# M360.net
KiCad netlist of a schematic drawn in EAGLE
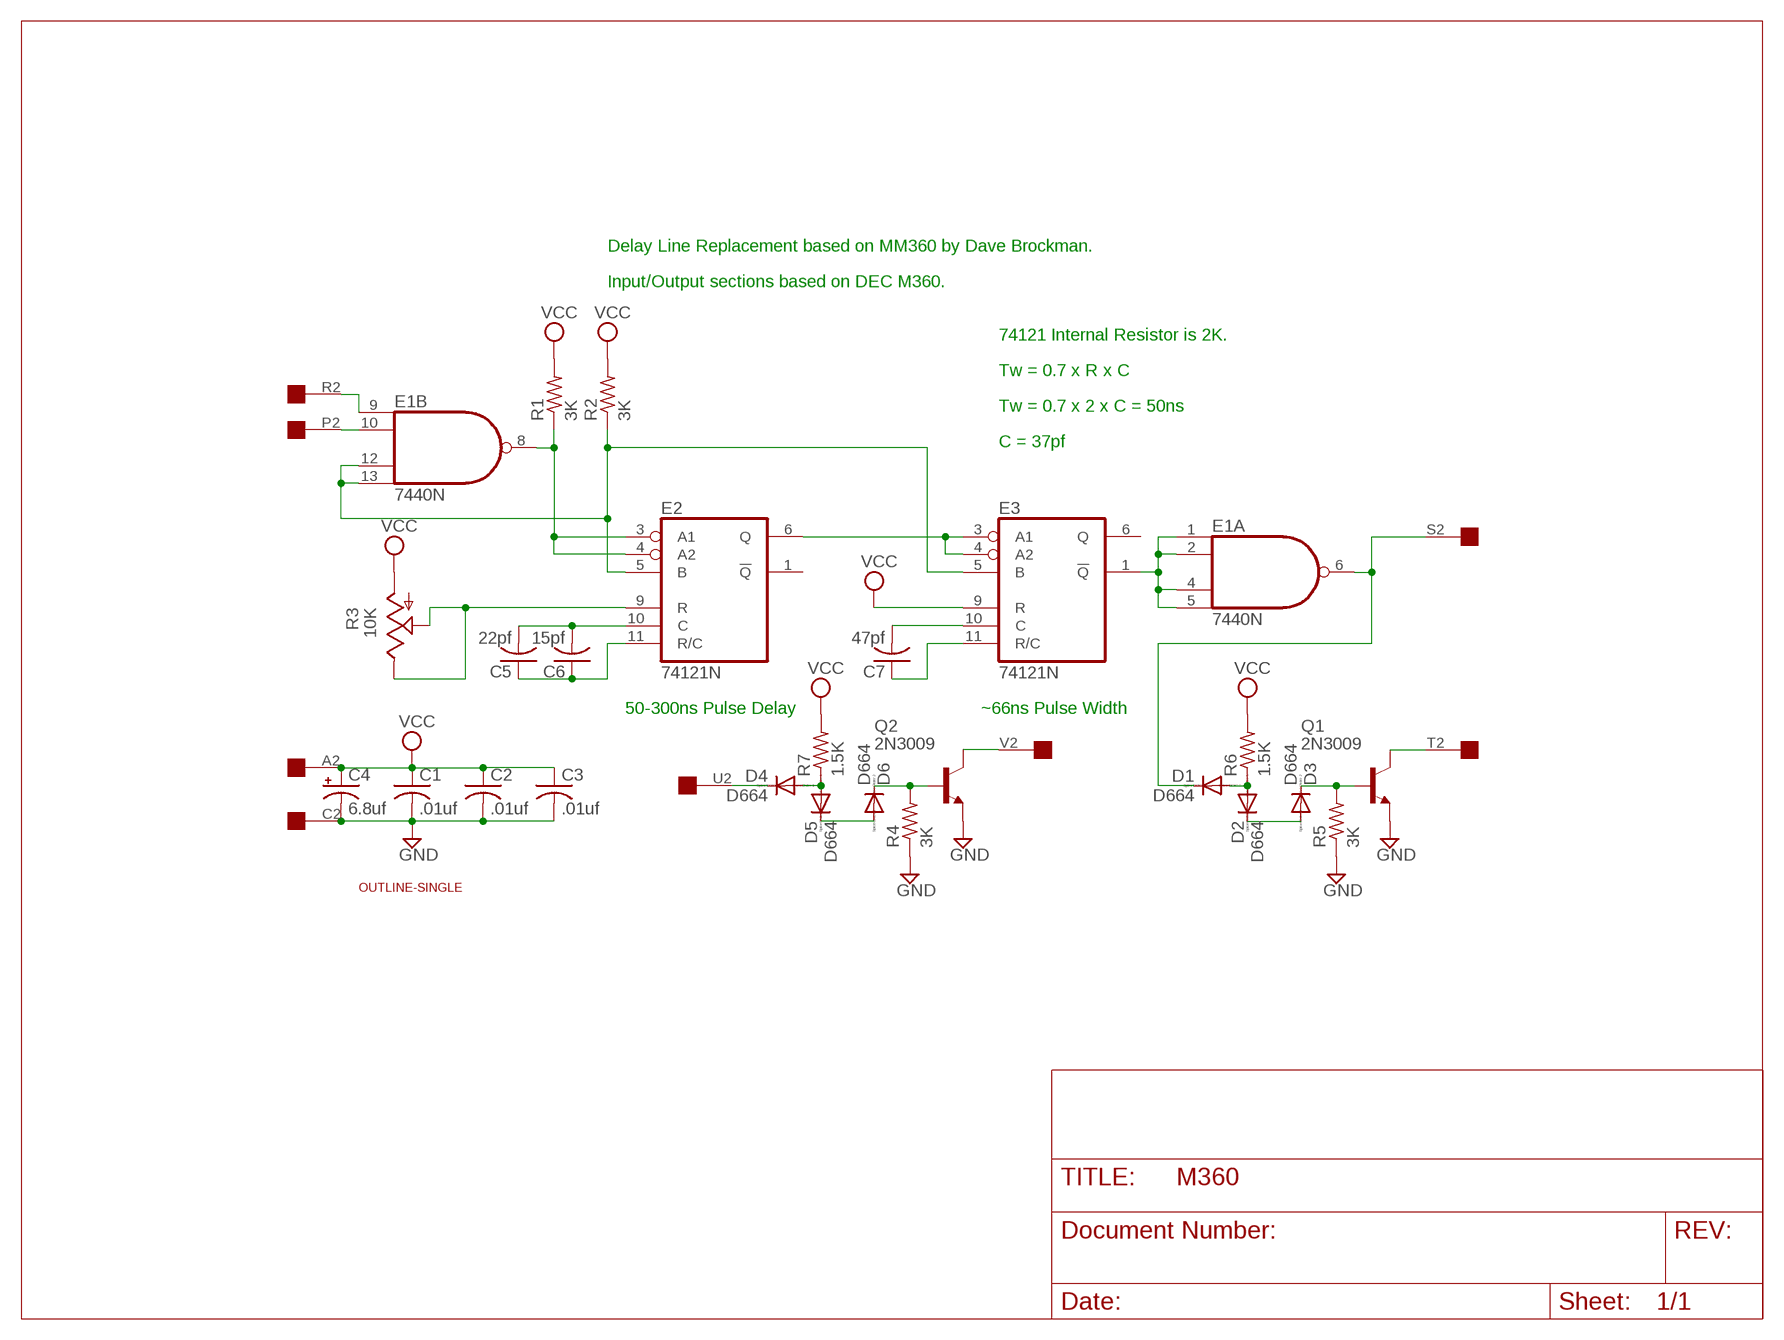
[diagram p0: schematic, sheet 1]

(export (version "E")
  (design (tool "Eeschema 10.0.6"))
  (components
    (comp (ref "C1")
      (value ".01uf")
      (footprint "eagle-import:C050-025X075")
      (libsource (lib "eagle-import") (part "C-US050-025X075"))
    )
    (comp (ref "C2")
      (value ".01uf")
      (footprint "eagle-import:C050-025X075")
      (libsource (lib "eagle-import") (part "C-US050-025X075"))
    )
    (comp (ref "C3")
      (value ".01uf")
      (footprint "eagle-import:C050-025X075")
      (libsource (lib "eagle-import") (part "C-US050-025X075"))
    )
    (comp (ref "C4")
      (value "6.8uf")
      (footprint "eagle-import:E15-5")
      (libsource (lib "eagle-import") (part "CPOL-USE15-5AXIAL"))
    )
    (comp (ref "C5")
      (value "22pf")
      (footprint "eagle-import:C050-025X075")
      (libsource (lib "eagle-import") (part "C-US050-025X075"))
    )
    (comp (ref "C6")
      (value "15pf")
      (footprint "eagle-import:C050-025X075")
      (libsource (lib "eagle-import") (part "C-US050-025X075"))
    )
    (comp (ref "C7")
      (value "47pf")
      (footprint "eagle-import:C050-025X075")
      (libsource (lib "eagle-import") (part "C-US050-025X075"))
    )
    (comp (ref "D1")
      (value "D664")
      (footprint "eagle-import:DO35-10")
      (libsource (lib "eagle-import") (part "1N4148DO35-10"))
    )
    (comp (ref "D2")
      (value "D664")
      (footprint "eagle-import:DO35-10")
      (libsource (lib "eagle-import") (part "1N4148DO35-10"))
    )
    (comp (ref "D3")
      (value "D664")
      (footprint "eagle-import:DO35-10")
      (libsource (lib "eagle-import") (part "1N4148DO35-10"))
    )
    (comp (ref "D4")
      (value "D664")
      (footprint "eagle-import:DO35-10")
      (libsource (lib "eagle-import") (part "1N4148DO35-10"))
    )
    (comp (ref "D5")
      (value "D664")
      (footprint "eagle-import:DO35-10")
      (libsource (lib "eagle-import") (part "1N4148DO35-10"))
    )
    (comp (ref "D6")
      (value "D664")
      (footprint "eagle-import:DO35-10")
      (libsource (lib "eagle-import") (part "1N4148DO35-10"))
    )
    (comp (ref "E1")
      (value "7440N")
      (footprint "eagle-import:DIL14")
      (libsource (lib "eagle-import") (part "7440NS"))
    )
    (comp (ref "E2")
      (value "74121N")
      (footprint "eagle-import:DIL14")
      (libsource (lib "eagle-import") (part "74121N"))
    )
    (comp (ref "E3")
      (value "74121N")
      (footprint "eagle-import:DIL14")
      (libsource (lib "eagle-import") (part "74121N"))
    )
    (comp (ref "Q1")
      (value "2N3009")
      (footprint "eagle-import:TO5")
      (libsource (lib "eagle-import") (part "2N2405"))
    )
    (comp (ref "Q2")
      (value "2N3009")
      (footprint "eagle-import:TO5")
      (libsource (lib "eagle-import") (part "2N2405"))
    )
    (comp (ref "R1")
      (value "3K")
      (footprint "eagle-import:0207_10")
      (libsource (lib "eagle-import") (part "R-US_0207/10"))
    )
    (comp (ref "R2")
      (value "3K")
      (footprint "eagle-import:0207_10")
      (libsource (lib "eagle-import") (part "R-US_0207/10"))
    )
    (comp (ref "R3")
      (value "10K")
      (footprint "eagle-import:PT-SPIN")
      (libsource (lib "eagle-import") (part "TRIM_US-PTSPIN"))
    )
    (comp (ref "R4")
      (value "3K")
      (footprint "eagle-import:0207_10")
      (libsource (lib "eagle-import") (part "R-US_0207/10"))
    )
    (comp (ref "R5")
      (value "3K")
      (footprint "eagle-import:0207_10")
      (libsource (lib "eagle-import") (part "R-US_0207/10"))
    )
    (comp (ref "R6")
      (value "1.5K")
      (footprint "eagle-import:0207_10")
      (libsource (lib "eagle-import") (part "R-US_0207/10"))
    )
    (comp (ref "R7")
      (value "1.5K")
      (footprint "eagle-import:0207_10")
      (libsource (lib "eagle-import") (part "R-US_0207/10"))
    )
    (comp (ref "U$1")
      (value "OUTLINE-SINGLE")
      (footprint "eagle-import:SINGLE")
      (libsource (lib "eagle-import") (part "OUTLINE-SINGLE"))
    )
    (comp (ref "U$3")
      (value "EDGE-1")
      (footprint "eagle-import:EDGE-CON1")
      (libsource (lib "eagle-import") (part "EDGE-1"))
    )
  )
  (nets
    (net (code "1") (name "GND") (class "Default")
      (node (ref "C1") (pin "2") (pinfunction "2_2") (pintype "passive"))
      (node (ref "C2") (pin "2") (pinfunction "2_2") (pintype "passive"))
      (node (ref "C3") (pin "2") (pinfunction "2_2") (pintype "passive"))
      (node (ref "C4") (pin "-") (pinfunction "-_-") (pintype "passive"))
      (node (ref "Q1") (pin "1") (pinfunction "E_1") (pintype "passive"))
      (node (ref "Q2") (pin "1") (pinfunction "E_1") (pintype "passive"))
      (node (ref "R4") (pin "1") (pinfunction "1_1") (pintype "passive"))
      (node (ref "R5") (pin "1") (pinfunction "1_1") (pintype "passive"))
      (node (ref "U$3") (pin "C2") (pinfunction "1_C2") (pintype "bidirectional"))
    )
    (net (code "2") (name "Net-(D1-PadA)") (class "Default")
      (node (ref "D1") (pin "A") (pinfunction "A_A") (pintype "passive"))
      (node (ref "D2") (pin "A") (pinfunction "A_A") (pintype "passive"))
      (node (ref "R6") (pin "1") (pinfunction "1_1") (pintype "passive"))
    )
    (net (code "3") (name "Net-(D2-PadC)") (class "Default")
      (node (ref "D2") (pin "C") (pinfunction "C_C") (pintype "passive"))
      (node (ref "D3") (pin "A") (pinfunction "A_A") (pintype "passive"))
    )
    (net (code "4") (name "Net-(D4-PadA)") (class "Default")
      (node (ref "D4") (pin "A") (pinfunction "A_A") (pintype "passive"))
      (node (ref "D5") (pin "A") (pinfunction "A_A") (pintype "passive"))
      (node (ref "R7") (pin "1") (pinfunction "1_1") (pintype "passive"))
    )
    (net (code "5") (name "Net-(D5-PadC)") (class "Default")
      (node (ref "D5") (pin "C") (pinfunction "C_C") (pintype "passive"))
      (node (ref "D6") (pin "A") (pinfunction "A_A") (pintype "passive"))
    )
    (net (code "6") (name "Net-(E1C-I0)") (class "Default")
      (node (ref "E1") (pin "1") (pinfunction "I0_1") (pintype "input"))
      (node (ref "E1") (pin "2") (pinfunction "I1_2") (pintype "input"))
      (node (ref "E1") (pin "4") (pinfunction "I2_4") (pintype "input"))
      (node (ref "E1") (pin "5") (pinfunction "I3_5") (pintype "input"))
      (node (ref "E3") (pin "1") (pinfunction "~{Q}_1") (pintype "output"))
    )
    (net (code "7") (name "Net-(E1C-O)") (class "Default")
      (node (ref "D1") (pin "C") (pinfunction "C_C") (pintype "passive"))
      (node (ref "E1") (pin "6") (pinfunction "O_6") (pintype "output"))
      (node (ref "U$3") (pin "S2") (pinfunction "1_S2") (pintype "bidirectional"))
    )
    (net (code "8") (name "Net-(E1D-I0)") (class "Default")
      (node (ref "E1") (pin "9") (pinfunction "I0_9") (pintype "input"))
      (node (ref "U$3") (pin "R2") (pinfunction "1_R2") (pintype "bidirectional"))
    )
    (net (code "9") (name "Net-(E1D-I1)") (class "Default")
      (node (ref "E1") (pin "10") (pinfunction "I1_10") (pintype "input"))
      (node (ref "U$3") (pin "P2") (pinfunction "1_P2") (pintype "bidirectional"))
    )
    (net (code "10") (name "Net-(E1D-I2)") (class "Default")
      (node (ref "E1") (pin "12") (pinfunction "I2_12") (pintype "input"))
      (node (ref "E1") (pin "13") (pinfunction "I3_13") (pintype "input"))
      (node (ref "E2") (pin "5") (pinfunction "B_5") (pintype "input"))
      (node (ref "E3") (pin "5") (pinfunction "B_5") (pintype "input"))
      (node (ref "R2") (pin "1") (pinfunction "1_1") (pintype "passive"))
    )
    (net (code "11") (name "Net-(E1D-O)") (class "Default")
      (node (ref "E1") (pin "8") (pinfunction "O_8") (pintype "output"))
      (node (ref "E2") (pin "3") (pinfunction "A1_3") (pintype "input"))
      (node (ref "E2") (pin "4") (pinfunction "A2_4") (pintype "input"))
      (node (ref "R1") (pin "1") (pinfunction "1_1") (pintype "passive"))
    )
    (net (code "12") (name "Net-(E2A-C)") (class "Default")
      (node (ref "C5") (pin "2") (pinfunction "2_2") (pintype "passive"))
      (node (ref "C6") (pin "2") (pinfunction "2_2") (pintype "passive"))
      (node (ref "E2") (pin "10") (pinfunction "C_10") (pintype "input"))
    )
    (net (code "13") (name "Net-(E2A-Q)") (class "Default")
      (node (ref "E2") (pin "6") (pinfunction "Q_6") (pintype "output"))
      (node (ref "E3") (pin "3") (pinfunction "A1_3") (pintype "input"))
      (node (ref "E3") (pin "4") (pinfunction "A2_4") (pintype "input"))
    )
    (net (code "14") (name "Net-(E2A-R)") (class "Default")
      (node (ref "E2") (pin "9") (pinfunction "R_9") (pintype "input"))
      (node (ref "R3") (pin "E") (pinfunction "E_E") (pintype "passive"))
      (node (ref "R3") (pin "S") (pinfunction "S_S") (pintype "passive"))
    )
    (net (code "15") (name "Net-(E2A-R{slash}C)") (class "Default")
      (node (ref "C5") (pin "1") (pinfunction "1_1") (pintype "passive"))
      (node (ref "C6") (pin "1") (pinfunction "1_1") (pintype "passive"))
      (node (ref "E2") (pin "11") (pinfunction "R/C_11") (pintype "input"))
    )
    (net (code "16") (name "Net-(E3A-C)") (class "Default")
      (node (ref "C7") (pin "2") (pinfunction "2_2") (pintype "passive"))
      (node (ref "E3") (pin "10") (pinfunction "C_10") (pintype "input"))
    )
    (net (code "17") (name "Net-(E3A-R{slash}C)") (class "Default")
      (node (ref "C7") (pin "1") (pinfunction "1_1") (pintype "passive"))
      (node (ref "E3") (pin "11") (pinfunction "R/C_11") (pintype "input"))
    )
    (net (code "18") (name "Net-(Q1-B)") (class "Default")
      (node (ref "D3") (pin "C") (pinfunction "C_C") (pintype "passive"))
      (node (ref "Q1") (pin "2") (pinfunction "B_2") (pintype "passive"))
      (node (ref "R5") (pin "2") (pinfunction "2_2") (pintype "passive"))
    )
    (net (code "19") (name "Net-(Q1-C)") (class "Default")
      (node (ref "Q1") (pin "3") (pinfunction "C_3") (pintype "passive"))
      (node (ref "U$3") (pin "T2") (pinfunction "1_T2") (pintype "bidirectional"))
    )
    (net (code "20") (name "Net-(Q2-B)") (class "Default")
      (node (ref "D6") (pin "C") (pinfunction "C_C") (pintype "passive"))
      (node (ref "Q2") (pin "2") (pinfunction "B_2") (pintype "passive"))
      (node (ref "R4") (pin "2") (pinfunction "2_2") (pintype "passive"))
    )
    (net (code "21") (name "Net-(Q2-C)") (class "Default")
      (node (ref "Q2") (pin "3") (pinfunction "C_3") (pintype "passive"))
      (node (ref "U$3") (pin "V2") (pinfunction "1_V2") (pintype "bidirectional"))
    )
    (net (code "22") (name "Net-(U$3Q-1)") (class "Default")
      (node (ref "D4") (pin "C") (pinfunction "C_C") (pintype "passive"))
      (node (ref "U$3") (pin "U2") (pinfunction "1_U2") (pintype "bidirectional"))
    )
    (net (code "23") (name "VCC") (class "Default")
      (node (ref "C1") (pin "1") (pinfunction "1_1") (pintype "passive"))
      (node (ref "C2") (pin "1") (pinfunction "1_1") (pintype "passive"))
      (node (ref "C3") (pin "1") (pinfunction "1_1") (pintype "passive"))
      (node (ref "C4") (pin "+") (pinfunction "+_+") (pintype "passive"))
      (node (ref "E3") (pin "9") (pinfunction "R_9") (pintype "input"))
      (node (ref "R1") (pin "2") (pinfunction "2_2") (pintype "passive"))
      (node (ref "R2") (pin "2") (pinfunction "2_2") (pintype "passive"))
      (node (ref "R3") (pin "A") (pinfunction "A_A") (pintype "passive"))
      (node (ref "R6") (pin "2") (pinfunction "2_2") (pintype "passive"))
      (node (ref "R7") (pin "2") (pinfunction "2_2") (pintype "passive"))
      (node (ref "U$3") (pin "A2") (pinfunction "1_A2") (pintype "bidirectional"))
    )
    (net (code "24") (name "unconnected-(E2A-~{Q}-Pad1)") (class "Default")
      (node (ref "E2") (pin "1") (pinfunction "~{Q}_1") (pintype "output"))
    )
    (net (code "25") (name "unconnected-(E3A-Q-Pad6)") (class "Default")
      (node (ref "E3") (pin "6") (pinfunction "Q_6") (pintype "output"))
    )
  )
)
